# power.net
KiCad netlist of a schematic drawn in Altium Designer
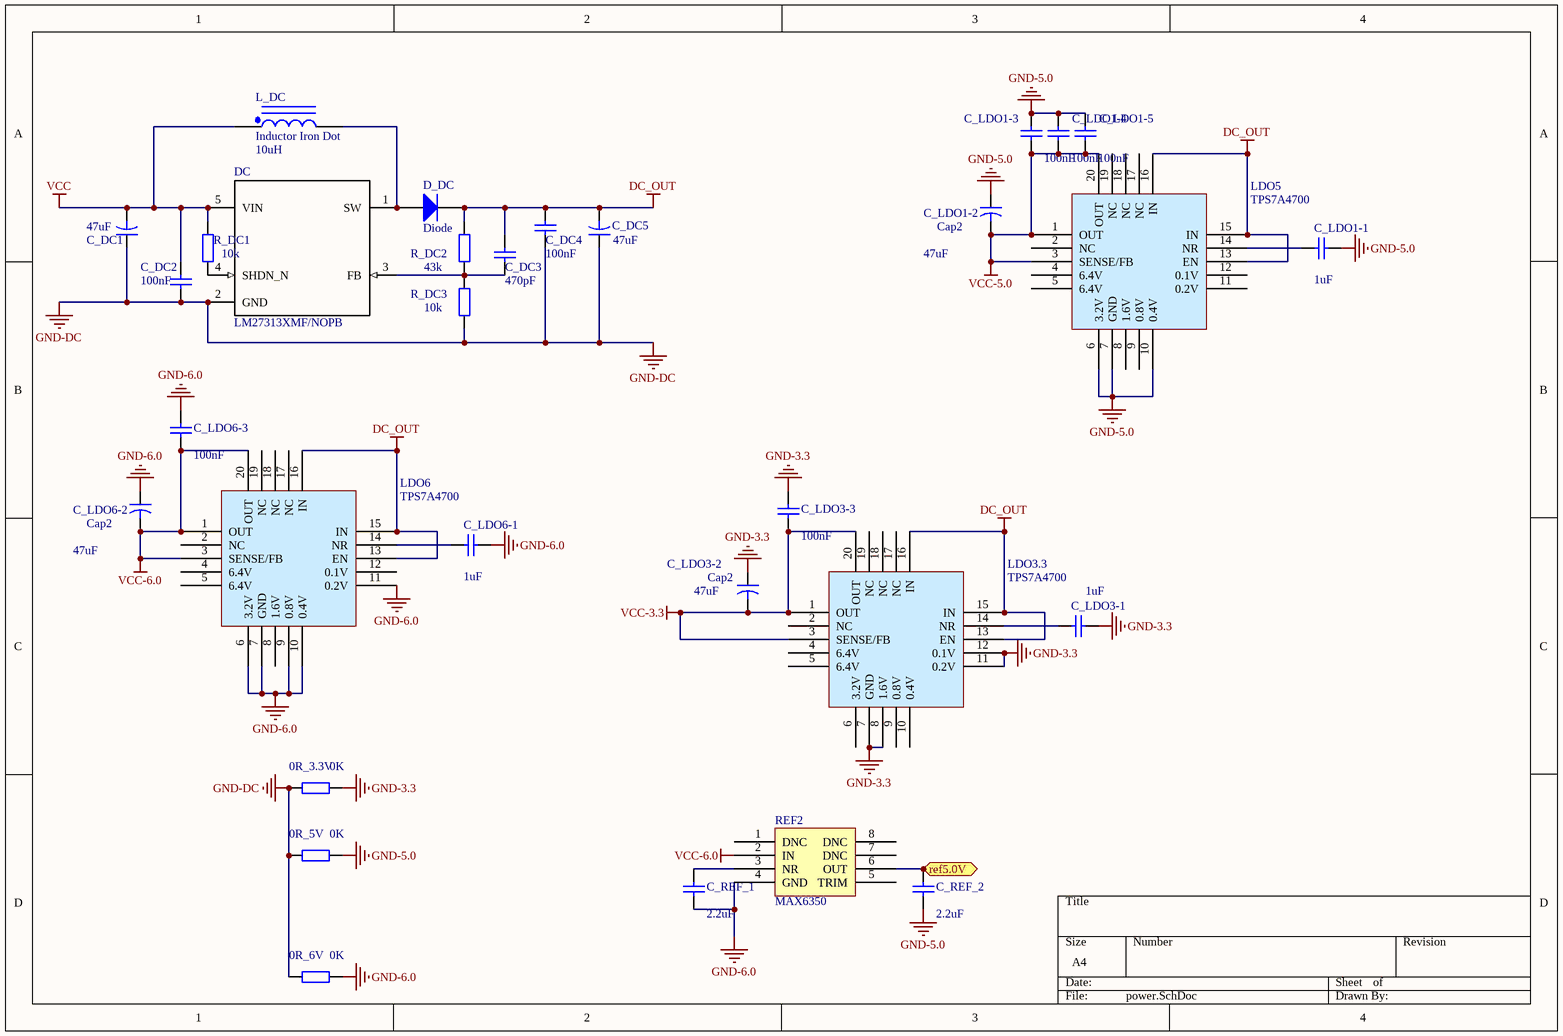
[diagram p0: power.SchDoc]

(export (version "E")
  (design (tool "Eeschema 10.0.6"))
  (components
    (comp (ref "0R_3.3V")
      (value "0K")
      (footprint "0603 - no")
      (description "Resistor")
      (fields (field (name "PUBLISHER") "Altium Limited"))
      (libsource (lib "") (part "Res2_1"))
    )
    (comp (ref "0R_5V")
      (value "0K")
      (footprint "0603 - no")
      (description "Resistor")
      (fields (field (name "PUBLISHER") "Altium Limited"))
      (libsource (lib "") (part "Res2_1"))
    )
    (comp (ref "0R_6V")
      (value "0K")
      (footprint "0603 - no")
      (description "Resistor")
      (fields (field (name "PUBLISHER") "Altium Limited"))
      (libsource (lib "") (part "Res2_1"))
    )
    (comp (ref "C_DC1")
      (value "47uF")
      (footprint "1210")
      (description "Capacitor")
      (fields (field (name "PUBLISHER") "Altium Limited"))
      (libsource (lib "Miscellaneous Devices") (part "Cap2"))
    )
    (comp (ref "C_DC2")
      (value "100nF")
      (footprint "0603 - no")
      (description "Capacitor")
      (fields (field (name "PUBLISHER") "Altium Limited"))
      (libsource (lib "Miscellaneous Devices") (part "Cap"))
    )
    (comp (ref "C_DC3")
      (value "470pF")
      (footprint "0603 - no")
      (description "Capacitor")
      (fields (field (name "PUBLISHER") "Altium Limited"))
      (libsource (lib "Miscellaneous Devices") (part "Cap"))
    )
    (comp (ref "C_DC4")
      (value "100nF")
      (footprint "0805")
      (description "Capacitor")
      (fields (field (name "PUBLISHER") "Altium Limited"))
      (libsource (lib "Miscellaneous Devices") (part "Cap"))
    )
    (comp (ref "C_DC5")
      (value "47uF")
      (footprint "1210")
      (description "Capacitor")
      (fields (field (name "PUBLISHER") "Altium Limited"))
      (libsource (lib "Miscellaneous Devices") (part "Cap2"))
    )
    (comp (ref "C_LDO1-1")
      (value "1uF")
      (footprint "0603 - no")
      (description "Capacitor")
      (fields (field (name "PUBLISHER") "Altium Limited"))
      (libsource (lib "Miscellaneous Devices") (part "Cap"))
    )
    (comp (ref "C_LDO1-2")
      (value "Cap2")
      (footprint "1210")
      (description "Capacitor")
      (fields (field (name "ALTIUM_VALUE") "47uF") (field (name "PUBLISHER") "Altium Limited"))
      (libsource (lib "Miscellaneous Devices") (part "Cap2"))
    )
    (comp (ref "C_LDO1-3")
      (value "100nF")
      (footprint "0805")
      (description "Capacitor")
      (fields (field (name "PUBLISHER") "Altium Limited"))
      (libsource (lib "Miscellaneous Devices") (part "Cap"))
    )
    (comp (ref "C_LDO1-4")
      (value "100nF")
      (footprint "0805")
      (description "Capacitor")
      (fields (field (name "PUBLISHER") "Altium Limited"))
      (libsource (lib "Miscellaneous Devices") (part "Cap"))
    )
    (comp (ref "C_LDO1-5")
      (value "100nF")
      (footprint "0805")
      (description "Capacitor")
      (fields (field (name "PUBLISHER") "Altium Limited"))
      (libsource (lib "Miscellaneous Devices") (part "Cap"))
    )
    (comp (ref "C_LDO3-1")
      (value "1uF")
      (footprint "0603 - no")
      (description "Capacitor")
      (fields (field (name "PUBLISHER") "Altium Limited"))
      (libsource (lib "Miscellaneous Devices") (part "Cap"))
    )
    (comp (ref "C_LDO3-2")
      (value "Cap2")
      (footprint "1210")
      (description "Capacitor")
      (fields (field (name "ALTIUM_VALUE") "47uF") (field (name "PUBLISHER") "Altium Limited"))
      (libsource (lib "Miscellaneous Devices") (part "Cap2"))
    )
    (comp (ref "C_LDO3-3")
      (value "100nF")
      (footprint "0805")
      (description "Capacitor")
      (fields (field (name "PUBLISHER") "Altium Limited"))
      (libsource (lib "Miscellaneous Devices") (part "Cap"))
    )
    (comp (ref "C_LDO6-1")
      (value "1uF")
      (footprint "0603 - no")
      (description "Capacitor")
      (fields (field (name "PUBLISHER") "Altium Limited"))
      (libsource (lib "Miscellaneous Devices") (part "Cap"))
    )
    (comp (ref "C_LDO6-2")
      (value "Cap2")
      (footprint "1210")
      (description "Capacitor")
      (fields (field (name "ALTIUM_VALUE") "47uF") (field (name "PUBLISHER") "Altium Limited"))
      (libsource (lib "Miscellaneous Devices") (part "Cap2"))
    )
    (comp (ref "C_LDO6-3")
      (value "100nF")
      (footprint "0805")
      (description "Capacitor")
      (fields (field (name "PUBLISHER") "Altium Limited"))
      (libsource (lib "Miscellaneous Devices") (part "Cap"))
    )
    (comp (ref "C_REF_1")
      (value "2.2uF")
      (footprint "0603 - no")
      (description "Capacitor")
      (fields (field (name "PUBLISHER") "Altium Limited"))
      (libsource (lib "Miscellaneous Devices") (part "Cap"))
    )
    (comp (ref "C_REF_2")
      (value "2.2uF")
      (footprint "0603 - no")
      (description "Capacitor")
      (fields (field (name "PUBLISHER") "Altium Limited"))
      (libsource (lib "Miscellaneous Devices") (part "Cap"))
    )
    (comp (ref "DC")
      (value "LM27313XMF/NOPB")
      (footprint "DBV0005A")
      (description "Imported")
      (fields (field (name "MANUFACTURER") "Texas Instruments"))
      (libsource (lib "complements") (part "LM27313XMF/NOPB"))
    )
    (comp (ref "D_DC")
      (value "Diode")
      (footprint "Diode-SOD123")
      (description "Default Diode")
      (fields (field (name "PUBLISHER") "Altium Limited"))
      (libsource (lib "Miscellaneous Devices") (part "Diode"))
    )
    (comp (ref "LDO3.3")
      (value "TPS7A4700")
      (footprint "TPS7A4700 - b")
      (libsource (lib "complements") (part "TPS7A4700"))
    )
    (comp (ref "LDO5")
      (value "TPS7A4700")
      (footprint "TPS7A4700 - b")
      (libsource (lib "complements") (part "TPS7A4700"))
    )
    (comp (ref "LDO6")
      (value "TPS7A4700")
      (footprint "TPS7A4700 - b")
      (libsource (lib "complements") (part "TPS7A4700"))
    )
    (comp (ref "L_DC")
      (value "Inductor Iron Dot")
      (footprint "GDNR5040")
      (description "Magnetic-Core Inductor with Winding Polarity Marking")
      (fields (field (name "ALTIUM_VALUE") "10uH") (field (name "PUBLISHER") "Altium Limited"))
      (libsource (lib "Miscellaneous Devices") (part "Inductor Iron Dot"))
    )
    (comp (ref "REF2") (value "MAX6350") (footprint "D8") (libsource (lib "complements") (part "MAX6350")))
    (comp (ref "R_DC1")
      (value "10k")
      (footprint "0603 - no")
      (description "Resistor")
      (fields (field (name "PUBLISHER") "Altium Limited"))
      (libsource (lib "Miscellaneous Devices") (part "Res2"))
    )
    (comp (ref "R_DC2")
      (value "43k")
      (footprint "0603 - no")
      (description "Resistor")
      (fields (field (name "PUBLISHER") "Altium Limited"))
      (libsource (lib "Miscellaneous Devices") (part "Res2"))
    )
    (comp (ref "R_DC3")
      (value "10k")
      (footprint "0603 - no")
      (description "Resistor")
      (fields (field (name "PUBLISHER") "Altium Limited"))
      (libsource (lib "Miscellaneous Devices") (part "Res2"))
    )
  )
  (nets
    (net (code "1") (name "/ref5.0V") (class "Default")
      (node (ref "C_REF_2") (pin "1") (pinfunction "1_1") (pintype "passive"))
      (node (ref "REF2") (pin "6") (pinfunction "OUT_6") (pintype "passive"))
    )
    (net (code "2") (name "DC_OUT") (class "Default")
      (node (ref "C_DC3") (pin "2") (pinfunction "2_2") (pintype "passive"))
      (node (ref "C_DC4") (pin "2") (pinfunction "2_2") (pintype "passive"))
      (node (ref "C_DC5") (pin "2") (pinfunction "2_2") (pintype "passive"))
      (node (ref "D_DC") (pin "2") (pinfunction "K_2") (pintype "passive"))
      (node (ref "LDO3.3") (pin "13") (pinfunction "EN_13") (pintype "passive"))
      (node (ref "LDO3.3") (pin "15") (pinfunction "IN_15") (pintype "passive"))
      (node (ref "LDO3.3") (pin "16") (pinfunction "IN_16") (pintype "passive"))
      (node (ref "LDO5") (pin "13") (pinfunction "EN_13") (pintype "passive"))
      (node (ref "LDO5") (pin "15") (pinfunction "IN_15") (pintype "passive"))
      (node (ref "LDO5") (pin "16") (pinfunction "IN_16") (pintype "passive"))
      (node (ref "LDO6") (pin "13") (pinfunction "EN_13") (pintype "passive"))
      (node (ref "LDO6") (pin "15") (pinfunction "IN_15") (pintype "passive"))
      (node (ref "LDO6") (pin "16") (pinfunction "IN_16") (pintype "passive"))
      (node (ref "R_DC2") (pin "2") (pinfunction "2_2") (pintype "passive"))
    )
    (net (code "3") (name "GND-3.3") (class "Default")
      (node (ref "0R_3.3V") (pin "1") (pinfunction "1_1") (pintype "passive"))
      (node (ref "C_LDO3-1") (pin "1") (pinfunction "1_1") (pintype "passive"))
      (node (ref "C_LDO3-2") (pin "1") (pinfunction "1_1") (pintype "passive"))
      (node (ref "C_LDO3-3") (pin "1") (pinfunction "1_1") (pintype "passive"))
      (node (ref "LDO3.3") (pin "11") (pinfunction "0.2V_11") (pintype "passive"))
      (node (ref "LDO3.3") (pin "12") (pinfunction "0.1V_12") (pintype "passive"))
      (node (ref "LDO3.3") (pin "7") (pinfunction "GND_7") (pintype "passive"))
      (node (ref "LDO3.3") (pin "8") (pinfunction "1.6V_8") (pintype "passive"))
    )
    (net (code "4") (name "GND-5.0") (class "Default")
      (node (ref "0R_5V") (pin "1") (pinfunction "1_1") (pintype "passive"))
      (node (ref "C_LDO1-1") (pin "1") (pinfunction "1_1") (pintype "passive"))
      (node (ref "C_LDO1-2") (pin "1") (pinfunction "1_1") (pintype "passive"))
      (node (ref "C_LDO1-3") (pin "1") (pinfunction "1_1") (pintype "passive"))
      (node (ref "C_LDO1-4") (pin "1") (pinfunction "1_1") (pintype "passive"))
      (node (ref "C_LDO1-5") (pin "1") (pinfunction "1_1") (pintype "passive"))
      (node (ref "C_REF_2") (pin "2") (pinfunction "2_2") (pintype "passive"))
      (node (ref "LDO5") (pin "10") (pinfunction "0.4V_10") (pintype "passive"))
      (node (ref "LDO5") (pin "6") (pinfunction "3.2V_6") (pintype "passive"))
      (node (ref "LDO5") (pin "7") (pinfunction "GND_7") (pintype "passive"))
    )
    (net (code "5") (name "GND-6.0") (class "Default")
      (node (ref "0R_6V") (pin "1") (pinfunction "1_1") (pintype "passive"))
      (node (ref "C_LDO6-1") (pin "1") (pinfunction "1_1") (pintype "passive"))
      (node (ref "C_LDO6-2") (pin "1") (pinfunction "1_1") (pintype "passive"))
      (node (ref "C_LDO6-3") (pin "1") (pinfunction "1_1") (pintype "passive"))
      (node (ref "C_REF_1") (pin "2") (pinfunction "2_2") (pintype "passive"))
      (node (ref "LDO6") (pin "10") (pinfunction "0.4V_10") (pintype "passive"))
      (node (ref "LDO6") (pin "11") (pinfunction "0.2V_11") (pintype "passive"))
      (node (ref "LDO6") (pin "6") (pinfunction "3.2V_6") (pintype "passive"))
      (node (ref "LDO6") (pin "7") (pinfunction "GND_7") (pintype "passive"))
      (node (ref "LDO6") (pin "9") (pinfunction "0.8V_9") (pintype "passive"))
      (node (ref "REF2") (pin "4") (pinfunction "GND_4") (pintype "passive"))
    )
    (net (code "6") (name "GND-DC") (class "Default")
      (node (ref "0R_3.3V") (pin "2") (pinfunction "2_2") (pintype "passive"))
      (node (ref "0R_5V") (pin "2") (pinfunction "2_2") (pintype "passive"))
      (node (ref "0R_6V") (pin "2") (pinfunction "2_2") (pintype "passive"))
      (node (ref "C_DC1") (pin "1") (pinfunction "1_1") (pintype "passive"))
      (node (ref "C_DC2") (pin "1") (pinfunction "1_1") (pintype "passive"))
      (node (ref "C_DC4") (pin "1") (pinfunction "1_1") (pintype "passive"))
      (node (ref "C_DC5") (pin "1") (pinfunction "1_1") (pintype "passive"))
      (node (ref "DC") (pin "2") (pinfunction "GND_2") (pintype "power_in"))
      (node (ref "R_DC3") (pin "1") (pinfunction "1_1") (pintype "passive"))
    )
    (net (code "7") (name "Net-(DC-FB)") (class "Default")
      (node (ref "C_DC3") (pin "1") (pinfunction "1_1") (pintype "passive"))
      (node (ref "DC") (pin "3") (pinfunction "FB_3") (pintype "input"))
      (node (ref "R_DC2") (pin "1") (pinfunction "1_1") (pintype "passive"))
      (node (ref "R_DC3") (pin "2") (pinfunction "2_2") (pintype "passive"))
    )
    (net (code "8") (name "Net-(DC-SHDN_N)") (class "Default")
      (node (ref "DC") (pin "4") (pinfunction "SHDN_N_4") (pintype "input"))
      (node (ref "R_DC1") (pin "1") (pinfunction "1_1") (pintype "passive"))
    )
    (net (code "9") (name "Net-(DC-SW)") (class "Default")
      (node (ref "DC") (pin "1") (pinfunction "SW_1") (pintype "power_in"))
      (node (ref "D_DC") (pin "1") (pinfunction "A_1") (pintype "passive"))
      (node (ref "L_DC") (pin "2") (pinfunction "2_2") (pintype "passive"))
    )
    (net (code "10") (name "Net-(LDO3.3-NR)") (class "Default")
      (node (ref "C_LDO3-1") (pin "2") (pinfunction "2_2") (pintype "passive"))
      (node (ref "LDO3.3") (pin "14") (pinfunction "NR_14") (pintype "passive"))
    )
    (net (code "11") (name "Net-(LDO5-NR)") (class "Default")
      (node (ref "C_LDO1-1") (pin "2") (pinfunction "2_2") (pintype "passive"))
      (node (ref "LDO5") (pin "14") (pinfunction "NR_14") (pintype "passive"))
    )
    (net (code "12") (name "Net-(LDO6-NR)") (class "Default")
      (node (ref "C_LDO6-1") (pin "2") (pinfunction "2_2") (pintype "passive"))
      (node (ref "LDO6") (pin "14") (pinfunction "NR_14") (pintype "passive"))
    )
    (net (code "13") (name "Net-(REF2-NR)") (class "Default")
      (node (ref "C_REF_1") (pin "1") (pinfunction "1_1") (pintype "passive"))
      (node (ref "REF2") (pin "3") (pinfunction "NR_3") (pintype "passive"))
    )
    (net (code "14") (name "VCC") (class "Default")
      (node (ref "C_DC1") (pin "2") (pinfunction "2_2") (pintype "passive"))
      (node (ref "C_DC2") (pin "2") (pinfunction "2_2") (pintype "passive"))
      (node (ref "DC") (pin "5") (pinfunction "VIN_5") (pintype "power_in"))
      (node (ref "L_DC") (pin "1") (pinfunction "1_1") (pintype "passive"))
      (node (ref "R_DC1") (pin "2") (pinfunction "2_2") (pintype "passive"))
    )
    (net (code "15") (name "VCC-3.3") (class "Default")
      (node (ref "C_LDO3-2") (pin "2") (pinfunction "2_2") (pintype "passive"))
      (node (ref "C_LDO3-3") (pin "2") (pinfunction "2_2") (pintype "passive"))
      (node (ref "LDO3.3") (pin "1") (pinfunction "OUT_1") (pintype "passive"))
      (node (ref "LDO3.3") (pin "20") (pinfunction "OUT_20") (pintype "passive"))
      (node (ref "LDO3.3") (pin "3") (pinfunction "SENSE/FB_3") (pintype "passive"))
    )
    (net (code "16") (name "VCC-5.0") (class "Default")
      (node (ref "C_LDO1-2") (pin "2") (pinfunction "2_2") (pintype "passive"))
      (node (ref "C_LDO1-3") (pin "2") (pinfunction "2_2") (pintype "passive"))
      (node (ref "C_LDO1-4") (pin "2") (pinfunction "2_2") (pintype "passive"))
      (node (ref "C_LDO1-5") (pin "2") (pinfunction "2_2") (pintype "passive"))
      (node (ref "LDO5") (pin "1") (pinfunction "OUT_1") (pintype "passive"))
      (node (ref "LDO5") (pin "20") (pinfunction "OUT_20") (pintype "passive"))
      (node (ref "LDO5") (pin "3") (pinfunction "SENSE/FB_3") (pintype "passive"))
    )
    (net (code "17") (name "VCC-6.0") (class "Default")
      (node (ref "C_LDO6-2") (pin "2") (pinfunction "2_2") (pintype "passive"))
      (node (ref "C_LDO6-3") (pin "2") (pinfunction "2_2") (pintype "passive"))
      (node (ref "LDO6") (pin "1") (pinfunction "OUT_1") (pintype "passive"))
      (node (ref "LDO6") (pin "20") (pinfunction "OUT_20") (pintype "passive"))
      (node (ref "LDO6") (pin "3") (pinfunction "SENSE/FB_3") (pintype "passive"))
      (node (ref "REF2") (pin "2") (pinfunction "IN_2") (pintype "passive"))
    )
    (net (code "18") (name "unconnected-(LDO3.3-0.4V-Pad10)") (class "Default")
      (node (ref "LDO3.3") (pin "10") (pinfunction "0.4V_10") (pintype "passive"))
    )
    (net (code "19") (name "unconnected-(LDO3.3-0.8V-Pad9)") (class "Default")
      (node (ref "LDO3.3") (pin "9") (pinfunction "0.8V_9") (pintype "passive"))
    )
    (net (code "20") (name "unconnected-(LDO3.3-3.2V-Pad6)") (class "Default")
      (node (ref "LDO3.3") (pin "6") (pinfunction "3.2V_6") (pintype "passive"))
    )
    (net (code "21") (name "unconnected-(LDO3.3-6.4V-Pad4)") (class "Default")
      (node (ref "LDO3.3") (pin "4") (pinfunction "6.4V_4") (pintype "passive"))
    )
    (net (code "22") (name "unconnected-(LDO3.3-6.4V-Pad5)") (class "Default")
      (node (ref "LDO3.3") (pin "5") (pinfunction "6.4V_5") (pintype "passive"))
    )
    (net (code "23") (name "unconnected-(LDO3.3-NC-Pad2)") (class "Default")
      (node (ref "LDO3.3") (pin "2") (pinfunction "NC_2") (pintype "passive"))
    )
    (net (code "24") (name "unconnected-(LDO3.3-NC-Pad17)") (class "Default")
      (node (ref "LDO3.3") (pin "17") (pinfunction "NC_17") (pintype "passive"))
    )
    (net (code "25") (name "unconnected-(LDO3.3-NC-Pad18)") (class "Default")
      (node (ref "LDO3.3") (pin "18") (pinfunction "NC_18") (pintype "passive"))
    )
    (net (code "26") (name "unconnected-(LDO3.3-NC-Pad19)") (class "Default")
      (node (ref "LDO3.3") (pin "19") (pinfunction "NC_19") (pintype "passive"))
    )
    (net (code "27") (name "unconnected-(LDO5-0.1V-Pad12)") (class "Default")
      (node (ref "LDO5") (pin "12") (pinfunction "0.1V_12") (pintype "passive"))
    )
    (net (code "28") (name "unconnected-(LDO5-0.2V-Pad11)") (class "Default")
      (node (ref "LDO5") (pin "11") (pinfunction "0.2V_11") (pintype "passive"))
    )
    (net (code "29") (name "unconnected-(LDO5-0.8V-Pad9)") (class "Default")
      (node (ref "LDO5") (pin "9") (pinfunction "0.8V_9") (pintype "passive"))
    )
    (net (code "30") (name "unconnected-(LDO5-1.6V-Pad8)") (class "Default")
      (node (ref "LDO5") (pin "8") (pinfunction "1.6V_8") (pintype "passive"))
    )
    (net (code "31") (name "unconnected-(LDO5-6.4V-Pad4)") (class "Default")
      (node (ref "LDO5") (pin "4") (pinfunction "6.4V_4") (pintype "passive"))
    )
    (net (code "32") (name "unconnected-(LDO5-6.4V-Pad5)") (class "Default")
      (node (ref "LDO5") (pin "5") (pinfunction "6.4V_5") (pintype "passive"))
    )
    (net (code "33") (name "unconnected-(LDO5-NC-Pad2)") (class "Default")
      (node (ref "LDO5") (pin "2") (pinfunction "NC_2") (pintype "passive"))
    )
    (net (code "34") (name "unconnected-(LDO5-NC-Pad17)") (class "Default")
      (node (ref "LDO5") (pin "17") (pinfunction "NC_17") (pintype "passive"))
    )
    (net (code "35") (name "unconnected-(LDO5-NC-Pad18)") (class "Default")
      (node (ref "LDO5") (pin "18") (pinfunction "NC_18") (pintype "passive"))
    )
    (net (code "36") (name "unconnected-(LDO5-NC-Pad19)") (class "Default")
      (node (ref "LDO5") (pin "19") (pinfunction "NC_19") (pintype "passive"))
    )
    (net (code "37") (name "unconnected-(LDO6-0.1V-Pad12)") (class "Default")
      (node (ref "LDO6") (pin "12") (pinfunction "0.1V_12") (pintype "passive"))
    )
    (net (code "38") (name "unconnected-(LDO6-1.6V-Pad8)") (class "Default")
      (node (ref "LDO6") (pin "8") (pinfunction "1.6V_8") (pintype "passive"))
    )
    (net (code "39") (name "unconnected-(LDO6-6.4V-Pad4)") (class "Default")
      (node (ref "LDO6") (pin "4") (pinfunction "6.4V_4") (pintype "passive"))
    )
    (net (code "40") (name "unconnected-(LDO6-6.4V-Pad5)") (class "Default")
      (node (ref "LDO6") (pin "5") (pinfunction "6.4V_5") (pintype "passive"))
    )
    (net (code "41") (name "unconnected-(LDO6-NC-Pad2)") (class "Default")
      (node (ref "LDO6") (pin "2") (pinfunction "NC_2") (pintype "passive"))
    )
    (net (code "42") (name "unconnected-(LDO6-NC-Pad17)") (class "Default")
      (node (ref "LDO6") (pin "17") (pinfunction "NC_17") (pintype "passive"))
    )
    (net (code "43") (name "unconnected-(LDO6-NC-Pad18)") (class "Default")
      (node (ref "LDO6") (pin "18") (pinfunction "NC_18") (pintype "passive"))
    )
    (net (code "44") (name "unconnected-(LDO6-NC-Pad19)") (class "Default")
      (node (ref "LDO6") (pin "19") (pinfunction "NC_19") (pintype "passive"))
    )
    (net (code "45") (name "unconnected-(REF2-DNC-Pad1)") (class "Default")
      (node (ref "REF2") (pin "1") (pinfunction "DNC_1") (pintype "passive"))
    )
    (net (code "46") (name "unconnected-(REF2-DNC-Pad7)") (class "Default")
      (node (ref "REF2") (pin "7") (pinfunction "DNC_7") (pintype "passive"))
    )
    (net (code "47") (name "unconnected-(REF2-DNC-Pad8)") (class "Default")
      (node (ref "REF2") (pin "8") (pinfunction "DNC_8") (pintype "passive"))
    )
    (net (code "48") (name "unconnected-(REF2-TRIM-Pad5)") (class "Default")
      (node (ref "REF2") (pin "5") (pinfunction "TRIM_5") (pintype "passive"))
    )
  )
)
